# Charge_switch.net
KiCad netlist of a schematic drawn in EAGLE
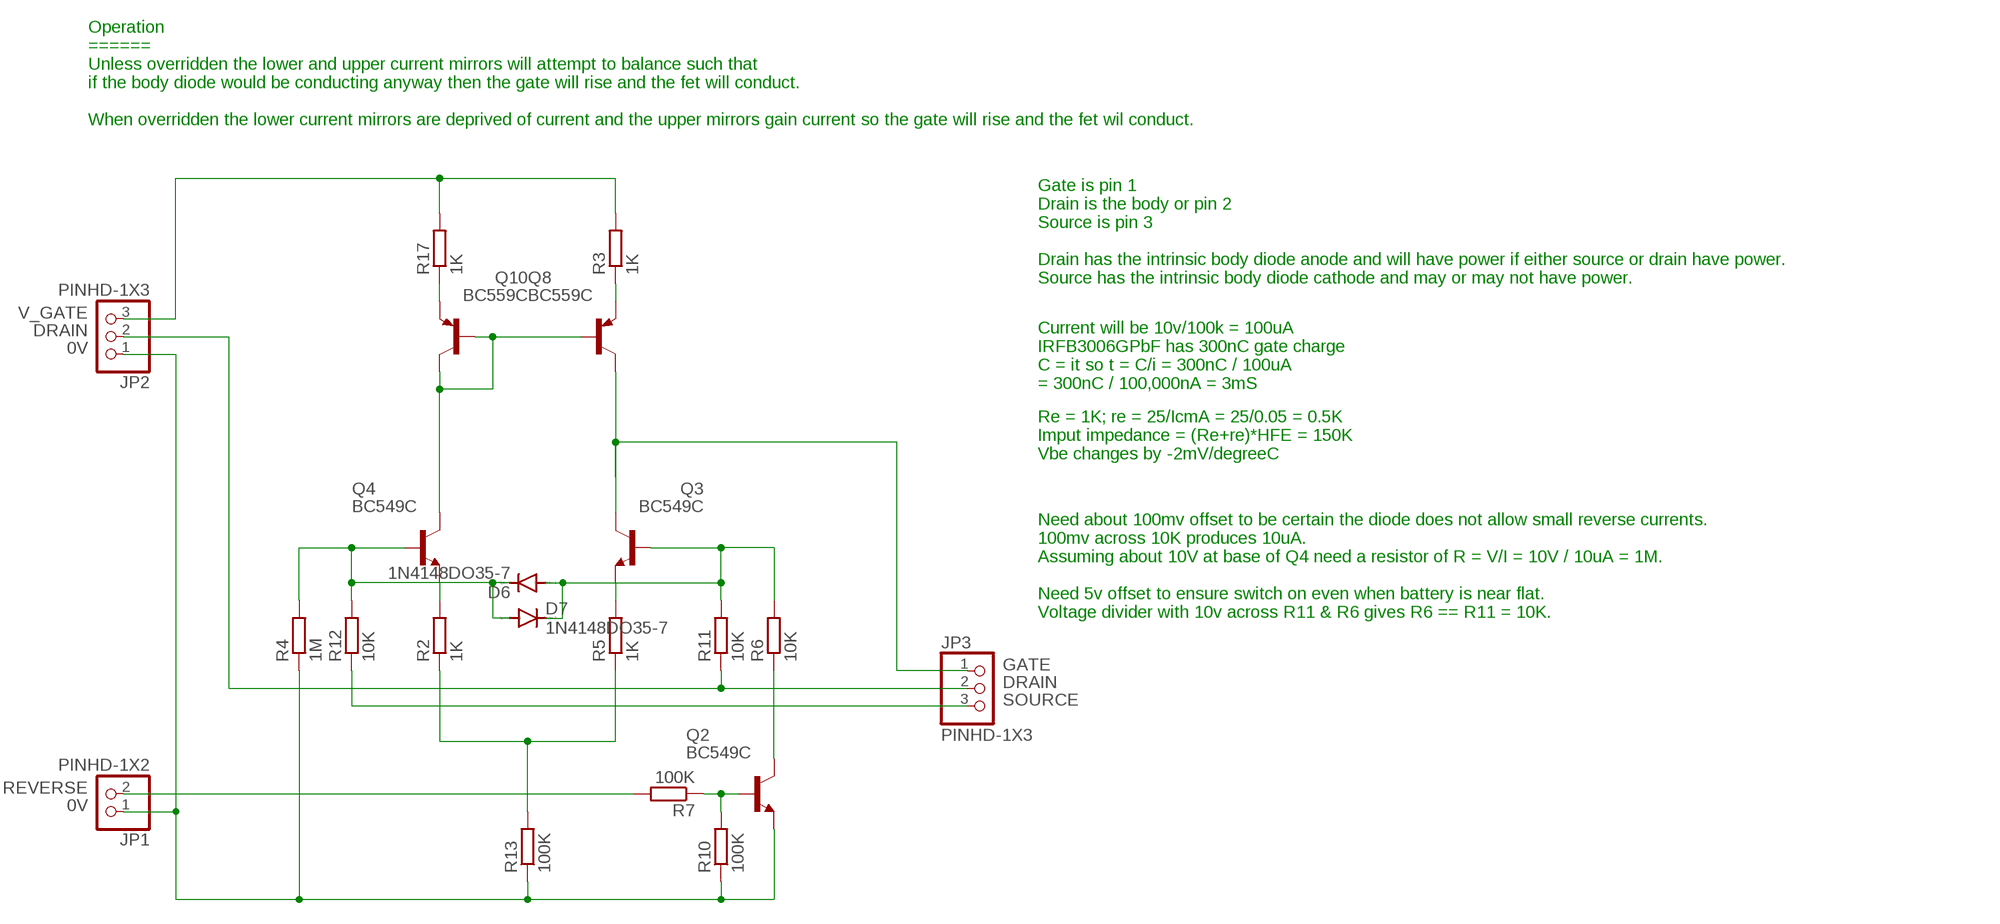
[diagram p0: schematic, sheet 1]

(export (version "E")
  (design (tool "Eeschema 10.0.6"))
  (components
    (comp (ref "D6")
      (value "1N4148DO35-7")
      (footprint "eagle-import:DO35-7")
      (libsource (lib "eagle-import") (part "1N4148DO35-7"))
    )
    (comp (ref "D7")
      (value "1N4148DO35-7")
      (footprint "eagle-import:DO35-7")
      (libsource (lib "eagle-import") (part "1N4148DO35-7"))
    )
    (comp (ref "JP1")
      (value "PINHD-1X2")
      (footprint "eagle-import:1X02")
      (libsource (lib "eagle-import") (part "PINHD-1X2"))
    )
    (comp (ref "JP2")
      (value "PINHD-1X3")
      (footprint "eagle-import:1X03")
      (libsource (lib "eagle-import") (part "PINHD-1X3"))
    )
    (comp (ref "JP3")
      (value "PINHD-1X3")
      (footprint "eagle-import:1X03")
      (libsource (lib "eagle-import") (part "PINHD-1X3"))
    )
    (comp (ref "Q2")
      (value "BC549C")
      (footprint "eagle-import:TO92-EBC")
      (libsource (lib "eagle-import") (part "BC549C"))
    )
    (comp (ref "Q3")
      (value "BC549C")
      (footprint "eagle-import:TO92-EBC")
      (libsource (lib "eagle-import") (part "BC549C"))
    )
    (comp (ref "Q4")
      (value "BC549C")
      (footprint "eagle-import:TO92-EBC")
      (libsource (lib "eagle-import") (part "BC549C"))
    )
    (comp (ref "Q8")
      (value "BC559C")
      (footprint "eagle-import:TO92-EBC")
      (libsource (lib "eagle-import") (part "BC559C"))
    )
    (comp (ref "Q10")
      (value "BC559C")
      (footprint "eagle-import:TO92-EBC")
      (libsource (lib "eagle-import") (part "BC559C"))
    )
    (comp (ref "R2")
      (value "1K")
      (footprint "eagle-import:0204_7")
      (libsource (lib "eagle-import") (part "R-EU_0204/7"))
    )
    (comp (ref "R3")
      (value "1K")
      (footprint "eagle-import:0204_7")
      (libsource (lib "eagle-import") (part "R-EU_0204/7"))
    )
    (comp (ref "R4")
      (value "1M")
      (footprint "eagle-import:0204_7")
      (libsource (lib "eagle-import") (part "R-EU_0204/7"))
    )
    (comp (ref "R5")
      (value "1K")
      (footprint "eagle-import:0204_7")
      (libsource (lib "eagle-import") (part "R-EU_0204/7"))
    )
    (comp (ref "R6")
      (value "10K")
      (footprint "eagle-import:0204_7")
      (libsource (lib "eagle-import") (part "R-EU_0204/7"))
    )
    (comp (ref "R7")
      (value "100K")
      (footprint "eagle-import:0204_7")
      (libsource (lib "eagle-import") (part "R-EU_0204/7"))
    )
    (comp (ref "R10")
      (value "100K")
      (footprint "eagle-import:0204_7")
      (libsource (lib "eagle-import") (part "R-EU_0204/7"))
    )
    (comp (ref "R11")
      (value "10K")
      (footprint "eagle-import:0204_7")
      (libsource (lib "eagle-import") (part "R-EU_0204/7"))
    )
    (comp (ref "R12")
      (value "10K")
      (footprint "eagle-import:0204_7")
      (libsource (lib "eagle-import") (part "R-EU_0204/7"))
    )
    (comp (ref "R13")
      (value "100K")
      (footprint "eagle-import:0204_7")
      (libsource (lib "eagle-import") (part "R-EU_0204/7"))
    )
    (comp (ref "R17")
      (value "1K")
      (footprint "eagle-import:0204_7")
      (libsource (lib "eagle-import") (part "R-EU_0204/7"))
    )
  )
  (nets
    (net (code "1") (name "/0V") (class "Default")
      (node (ref "JP1") (pin "1") (pinfunction "1_1") (pintype "passive"))
      (node (ref "JP2") (pin "1") (pinfunction "1_1") (pintype "passive"))
      (node (ref "Q2") (pin "E") (pinfunction "E_E") (pintype "passive"))
      (node (ref "R10") (pin "1") (pinfunction "1_1") (pintype "passive"))
      (node (ref "R13") (pin "1") (pinfunction "1_1") (pintype "passive"))
      (node (ref "R4") (pin "1") (pinfunction "1_1") (pintype "passive"))
    )
    (net (code "2") (name "/DRAIN") (class "Default")
      (node (ref "JP2") (pin "2") (pinfunction "2_2") (pintype "passive"))
      (node (ref "JP3") (pin "2") (pinfunction "2_2") (pintype "passive"))
      (node (ref "R11") (pin "1") (pinfunction "1_1") (pintype "passive"))
    )
    (net (code "3") (name "/GATE") (class "Default")
      (node (ref "JP3") (pin "1") (pinfunction "1_1") (pintype "passive"))
      (node (ref "Q3") (pin "C") (pinfunction "C_C") (pintype "passive"))
      (node (ref "Q8") (pin "C") (pinfunction "C_C") (pintype "passive"))
    )
    (net (code "4") (name "/REVERSE") (class "Default")
      (node (ref "JP1") (pin "2") (pinfunction "2_2") (pintype "passive"))
      (node (ref "R7") (pin "2") (pinfunction "2_2") (pintype "passive"))
    )
    (net (code "5") (name "/SOURCE") (class "Default")
      (node (ref "JP3") (pin "3") (pinfunction "3_3") (pintype "passive"))
      (node (ref "R12") (pin "1") (pinfunction "1_1") (pintype "passive"))
    )
    (net (code "6") (name "/V_GATE") (class "Default")
      (node (ref "JP2") (pin "3") (pinfunction "3_3") (pintype "passive"))
      (node (ref "R17") (pin "2") (pinfunction "2_2") (pintype "passive"))
      (node (ref "R3") (pin "2") (pinfunction "2_2") (pintype "passive"))
    )
    (net (code "7") (name "Net-(D6-PadA)") (class "Default")
      (node (ref "D6") (pin "A") (pinfunction "A_A") (pintype "passive"))
      (node (ref "D7") (pin "C") (pinfunction "C_C") (pintype "passive"))
      (node (ref "Q3") (pin "B") (pinfunction "B_B") (pintype "passive"))
      (node (ref "R11") (pin "2") (pinfunction "2_2") (pintype "passive"))
      (node (ref "R6") (pin "2") (pinfunction "2_2") (pintype "passive"))
    )
    (net (code "8") (name "Net-(D6-PadC)") (class "Default")
      (node (ref "D6") (pin "C") (pinfunction "C_C") (pintype "passive"))
      (node (ref "D7") (pin "A") (pinfunction "A_A") (pintype "passive"))
      (node (ref "Q4") (pin "B") (pinfunction "B_B") (pintype "passive"))
      (node (ref "R12") (pin "2") (pinfunction "2_2") (pintype "passive"))
      (node (ref "R4") (pin "2") (pinfunction "2_2") (pintype "passive"))
    )
    (net (code "9") (name "Net-(Q2-PadB)") (class "Default")
      (node (ref "Q2") (pin "B") (pinfunction "B_B") (pintype "passive"))
      (node (ref "R10") (pin "2") (pinfunction "2_2") (pintype "passive"))
      (node (ref "R7") (pin "1") (pinfunction "1_1") (pintype "passive"))
    )
    (net (code "10") (name "Net-(Q2-PadC)") (class "Default")
      (node (ref "Q2") (pin "C") (pinfunction "C_C") (pintype "passive"))
      (node (ref "R6") (pin "1") (pinfunction "1_1") (pintype "passive"))
    )
    (net (code "11") (name "Net-(Q3-PadE)") (class "Default")
      (node (ref "Q3") (pin "E") (pinfunction "E_E") (pintype "passive"))
      (node (ref "R5") (pin "2") (pinfunction "2_2") (pintype "passive"))
    )
    (net (code "12") (name "Net-(Q4-PadE)") (class "Default")
      (node (ref "Q4") (pin "E") (pinfunction "E_E") (pintype "passive"))
      (node (ref "R2") (pin "2") (pinfunction "2_2") (pintype "passive"))
    )
    (net (code "13") (name "Net-(Q8-PadE)") (class "Default")
      (node (ref "Q8") (pin "E") (pinfunction "E_E") (pintype "passive"))
      (node (ref "R3") (pin "1") (pinfunction "1_1") (pintype "passive"))
    )
    (net (code "14") (name "Net-(Q10-PadB)") (class "Default")
      (node (ref "Q10") (pin "B") (pinfunction "B_B") (pintype "passive"))
      (node (ref "Q10") (pin "C") (pinfunction "C_C") (pintype "passive"))
      (node (ref "Q4") (pin "C") (pinfunction "C_C") (pintype "passive"))
      (node (ref "Q8") (pin "B") (pinfunction "B_B") (pintype "passive"))
    )
    (net (code "15") (name "Net-(Q10-PadE)") (class "Default")
      (node (ref "Q10") (pin "E") (pinfunction "E_E") (pintype "passive"))
      (node (ref "R17") (pin "1") (pinfunction "1_1") (pintype "passive"))
    )
    (net (code "16") (name "Net-(R13-Pad2)") (class "Default")
      (node (ref "R13") (pin "2") (pinfunction "2_2") (pintype "passive"))
      (node (ref "R2") (pin "1") (pinfunction "1_1") (pintype "passive"))
      (node (ref "R5") (pin "1") (pinfunction "1_1") (pintype "passive"))
    )
  )
)
